# 7segment.net
KiCad netlist of a schematic drawn in EAGLE
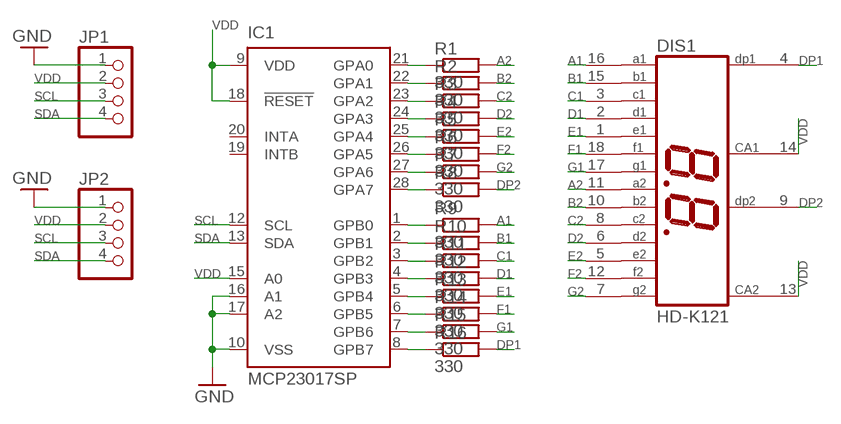
[diagram p0: schematic, sheet 1]

(export (version "E")
  (design (tool "Eeschema 10.0.6"))
  (components
    (comp (ref "DIS1")
      (value "HD-K121")
      (footprint "eagle-import:HDSP-R")
      (libsource (lib "eagle-import") (part "HD-K121"))
    )
    (comp (ref "IC1")
      (value "MCP23017SP")
      (footprint "eagle-import:DIL28-3")
      (fields (field (name "MF") "MICROCHIP") (field (name "MPN") "MCP23017-E/SP"))
      (libsource (lib "eagle-import") (part "MCP23017SP"))
    )
    (comp (ref "JP1")
      (value "PINHD-1X4")
      (footprint "eagle-import:1X04")
      (libsource (lib "eagle-import") (part "PINHD-1X4"))
    )
    (comp (ref "JP2")
      (value "PINHD-1X4")
      (footprint "eagle-import:1X04")
      (libsource (lib "eagle-import") (part "PINHD-1X4"))
    )
    (comp (ref "R1")
      (value "330")
      (footprint "eagle-import:0204V")
      (libsource (lib "eagle-import") (part "R-EU_0204/2V"))
    )
    (comp (ref "R2")
      (value "330")
      (footprint "eagle-import:0204V")
      (libsource (lib "eagle-import") (part "R-EU_0204/2V"))
    )
    (comp (ref "R3")
      (value "330")
      (footprint "eagle-import:0204V")
      (libsource (lib "eagle-import") (part "R-EU_0204/2V"))
    )
    (comp (ref "R4")
      (value "330")
      (footprint "eagle-import:0204V")
      (libsource (lib "eagle-import") (part "R-EU_0204/2V"))
    )
    (comp (ref "R5")
      (value "330")
      (footprint "eagle-import:0204V")
      (libsource (lib "eagle-import") (part "R-EU_0204/2V"))
    )
    (comp (ref "R6")
      (value "330")
      (footprint "eagle-import:0204V")
      (libsource (lib "eagle-import") (part "R-EU_0204/2V"))
    )
    (comp (ref "R7")
      (value "330")
      (footprint "eagle-import:0204V")
      (libsource (lib "eagle-import") (part "R-EU_0204/2V"))
    )
    (comp (ref "R8")
      (value "330")
      (footprint "eagle-import:0204V")
      (libsource (lib "eagle-import") (part "R-EU_0204/2V"))
    )
    (comp (ref "R9")
      (value "330")
      (footprint "eagle-import:0204V")
      (libsource (lib "eagle-import") (part "R-EU_0204/2V"))
    )
    (comp (ref "R10")
      (value "330")
      (footprint "eagle-import:0204V")
      (libsource (lib "eagle-import") (part "R-EU_0204/2V"))
    )
    (comp (ref "R11")
      (value "330")
      (footprint "eagle-import:0204V")
      (libsource (lib "eagle-import") (part "R-EU_0204/2V"))
    )
    (comp (ref "R12")
      (value "330")
      (footprint "eagle-import:0204V")
      (libsource (lib "eagle-import") (part "R-EU_0204/2V"))
    )
    (comp (ref "R13")
      (value "330")
      (footprint "eagle-import:0204V")
      (libsource (lib "eagle-import") (part "R-EU_0204/2V"))
    )
    (comp (ref "R14")
      (value "330")
      (footprint "eagle-import:0204V")
      (libsource (lib "eagle-import") (part "R-EU_0204/2V"))
    )
    (comp (ref "R15")
      (value "330")
      (footprint "eagle-import:0204V")
      (libsource (lib "eagle-import") (part "R-EU_0204/2V"))
    )
    (comp (ref "R16")
      (value "330")
      (footprint "eagle-import:0204V")
      (libsource (lib "eagle-import") (part "R-EU_0204/2V"))
    )
  )
  (nets
    (net (code "1") (name "/A1") (class "Default")
      (node (ref "DIS1") (pin "16") (pinfunction "A1_16") (pintype "passive"))
      (node (ref "R9") (pin "2") (pinfunction "2_2") (pintype "passive"))
    )
    (net (code "2") (name "/A2") (class "Default")
      (node (ref "DIS1") (pin "11") (pinfunction "A2_11") (pintype "passive"))
      (node (ref "R1") (pin "2") (pinfunction "2_2") (pintype "passive"))
    )
    (net (code "3") (name "/B1") (class "Default")
      (node (ref "DIS1") (pin "15") (pinfunction "B1_15") (pintype "passive"))
      (node (ref "R10") (pin "2") (pinfunction "2_2") (pintype "passive"))
    )
    (net (code "4") (name "/B2") (class "Default")
      (node (ref "DIS1") (pin "10") (pinfunction "B2_10") (pintype "passive"))
      (node (ref "R2") (pin "2") (pinfunction "2_2") (pintype "passive"))
    )
    (net (code "5") (name "/C1") (class "Default")
      (node (ref "DIS1") (pin "3") (pinfunction "C1_3") (pintype "passive"))
      (node (ref "R11") (pin "2") (pinfunction "2_2") (pintype "passive"))
    )
    (net (code "6") (name "/C2") (class "Default")
      (node (ref "DIS1") (pin "8") (pinfunction "C2_8") (pintype "passive"))
      (node (ref "R3") (pin "2") (pinfunction "2_2") (pintype "passive"))
    )
    (net (code "7") (name "/D1") (class "Default")
      (node (ref "DIS1") (pin "2") (pinfunction "D1_2") (pintype "passive"))
      (node (ref "R12") (pin "2") (pinfunction "2_2") (pintype "passive"))
    )
    (net (code "8") (name "/D2") (class "Default")
      (node (ref "DIS1") (pin "6") (pinfunction "D2_6") (pintype "passive"))
      (node (ref "R4") (pin "2") (pinfunction "2_2") (pintype "passive"))
    )
    (net (code "9") (name "/DP1") (class "Default")
      (node (ref "DIS1") (pin "4") (pinfunction "DP1_4") (pintype "passive"))
      (node (ref "R16") (pin "2") (pinfunction "2_2") (pintype "passive"))
    )
    (net (code "10") (name "/DP2") (class "Default")
      (node (ref "DIS1") (pin "9") (pinfunction "DP2_9") (pintype "passive"))
      (node (ref "R8") (pin "2") (pinfunction "2_2") (pintype "passive"))
    )
    (net (code "11") (name "/E1") (class "Default")
      (node (ref "DIS1") (pin "1") (pinfunction "E1_1") (pintype "passive"))
      (node (ref "R13") (pin "2") (pinfunction "2_2") (pintype "passive"))
    )
    (net (code "12") (name "/E2") (class "Default")
      (node (ref "DIS1") (pin "5") (pinfunction "E2_5") (pintype "passive"))
      (node (ref "R5") (pin "2") (pinfunction "2_2") (pintype "passive"))
    )
    (net (code "13") (name "/F1") (class "Default")
      (node (ref "DIS1") (pin "18") (pinfunction "F1_18") (pintype "passive"))
      (node (ref "R14") (pin "2") (pinfunction "2_2") (pintype "passive"))
    )
    (net (code "14") (name "/F2") (class "Default")
      (node (ref "DIS1") (pin "12") (pinfunction "F2_12") (pintype "passive"))
      (node (ref "R6") (pin "2") (pinfunction "2_2") (pintype "passive"))
    )
    (net (code "15") (name "/G1") (class "Default")
      (node (ref "DIS1") (pin "17") (pinfunction "G1_17") (pintype "passive"))
      (node (ref "R15") (pin "2") (pinfunction "2_2") (pintype "passive"))
    )
    (net (code "16") (name "/G2") (class "Default")
      (node (ref "DIS1") (pin "7") (pinfunction "G2_7") (pintype "passive"))
      (node (ref "R7") (pin "2") (pinfunction "2_2") (pintype "passive"))
    )
    (net (code "17") (name "/SCL") (class "Default")
      (node (ref "IC1") (pin "12") (pinfunction "SCL_12") (pintype "input"))
      (node (ref "JP1") (pin "3") (pinfunction "3_3") (pintype "passive"))
      (node (ref "JP2") (pin "3") (pinfunction "3_3") (pintype "passive"))
    )
    (net (code "18") (name "/SDA") (class "Default")
      (node (ref "IC1") (pin "13") (pinfunction "SDA_13") (pintype "bidirectional"))
      (node (ref "JP1") (pin "4") (pinfunction "4_4") (pintype "passive"))
      (node (ref "JP2") (pin "4") (pinfunction "4_4") (pintype "passive"))
    )
    (net (code "19") (name "/VDD") (class "Default")
      (node (ref "DIS1") (pin "13") (pinfunction "CA2_13") (pintype "passive"))
      (node (ref "DIS1") (pin "14") (pinfunction "CA1_14") (pintype "passive"))
      (node (ref "IC1") (pin "15") (pinfunction "A0_15") (pintype "input"))
      (node (ref "IC1") (pin "18") (pinfunction "~{RESET}_18") (pintype "input"))
      (node (ref "IC1") (pin "9") (pinfunction "VDD_9") (pintype "power_in"))
      (node (ref "JP1") (pin "2") (pinfunction "2_2") (pintype "passive"))
      (node (ref "JP2") (pin "2") (pinfunction "2_2") (pintype "passive"))
    )
    (net (code "20") (name "GND") (class "Default")
      (node (ref "IC1") (pin "10") (pinfunction "VSS_10") (pintype "power_in"))
      (node (ref "IC1") (pin "16") (pinfunction "A1_16") (pintype "input"))
      (node (ref "IC1") (pin "17") (pinfunction "A2_17") (pintype "input"))
      (node (ref "JP1") (pin "1") (pinfunction "1_1") (pintype "passive"))
      (node (ref "JP2") (pin "1") (pinfunction "1_1") (pintype "passive"))
    )
    (net (code "21") (name "Net-(IC1-GPA0)") (class "Default")
      (node (ref "IC1") (pin "21") (pinfunction "GPA0_21") (pintype "bidirectional"))
      (node (ref "R1") (pin "1") (pinfunction "1_1") (pintype "passive"))
    )
    (net (code "22") (name "Net-(IC1-GPA1)") (class "Default")
      (node (ref "IC1") (pin "22") (pinfunction "GPA1_22") (pintype "bidirectional"))
      (node (ref "R2") (pin "1") (pinfunction "1_1") (pintype "passive"))
    )
    (net (code "23") (name "Net-(IC1-GPA2)") (class "Default")
      (node (ref "IC1") (pin "23") (pinfunction "GPA2_23") (pintype "bidirectional"))
      (node (ref "R3") (pin "1") (pinfunction "1_1") (pintype "passive"))
    )
    (net (code "24") (name "Net-(IC1-GPA3)") (class "Default")
      (node (ref "IC1") (pin "24") (pinfunction "GPA3_24") (pintype "bidirectional"))
      (node (ref "R4") (pin "1") (pinfunction "1_1") (pintype "passive"))
    )
    (net (code "25") (name "Net-(IC1-GPA4)") (class "Default")
      (node (ref "IC1") (pin "25") (pinfunction "GPA4_25") (pintype "bidirectional"))
      (node (ref "R5") (pin "1") (pinfunction "1_1") (pintype "passive"))
    )
    (net (code "26") (name "Net-(IC1-GPA5)") (class "Default")
      (node (ref "IC1") (pin "26") (pinfunction "GPA5_26") (pintype "bidirectional"))
      (node (ref "R6") (pin "1") (pinfunction "1_1") (pintype "passive"))
    )
    (net (code "27") (name "Net-(IC1-GPA6)") (class "Default")
      (node (ref "IC1") (pin "27") (pinfunction "GPA6_27") (pintype "bidirectional"))
      (node (ref "R7") (pin "1") (pinfunction "1_1") (pintype "passive"))
    )
    (net (code "28") (name "Net-(IC1-GPA7)") (class "Default")
      (node (ref "IC1") (pin "28") (pinfunction "GPA7_28") (pintype "bidirectional"))
      (node (ref "R8") (pin "1") (pinfunction "1_1") (pintype "passive"))
    )
    (net (code "29") (name "Net-(IC1-GPB0)") (class "Default")
      (node (ref "IC1") (pin "1") (pinfunction "GPB0_1") (pintype "bidirectional"))
      (node (ref "R9") (pin "1") (pinfunction "1_1") (pintype "passive"))
    )
    (net (code "30") (name "Net-(IC1-GPB1)") (class "Default")
      (node (ref "IC1") (pin "2") (pinfunction "GPB1_2") (pintype "bidirectional"))
      (node (ref "R10") (pin "1") (pinfunction "1_1") (pintype "passive"))
    )
    (net (code "31") (name "Net-(IC1-GPB2)") (class "Default")
      (node (ref "IC1") (pin "3") (pinfunction "GPB2_3") (pintype "bidirectional"))
      (node (ref "R11") (pin "1") (pinfunction "1_1") (pintype "passive"))
    )
    (net (code "32") (name "Net-(IC1-GPB3)") (class "Default")
      (node (ref "IC1") (pin "4") (pinfunction "GPB3_4") (pintype "bidirectional"))
      (node (ref "R12") (pin "1") (pinfunction "1_1") (pintype "passive"))
    )
    (net (code "33") (name "Net-(IC1-GPB4)") (class "Default")
      (node (ref "IC1") (pin "5") (pinfunction "GPB4_5") (pintype "bidirectional"))
      (node (ref "R13") (pin "1") (pinfunction "1_1") (pintype "passive"))
    )
    (net (code "34") (name "Net-(IC1-GPB5)") (class "Default")
      (node (ref "IC1") (pin "6") (pinfunction "GPB5_6") (pintype "bidirectional"))
      (node (ref "R14") (pin "1") (pinfunction "1_1") (pintype "passive"))
    )
    (net (code "35") (name "Net-(IC1-GPB6)") (class "Default")
      (node (ref "IC1") (pin "7") (pinfunction "GPB6_7") (pintype "bidirectional"))
      (node (ref "R15") (pin "1") (pinfunction "1_1") (pintype "passive"))
    )
    (net (code "36") (name "Net-(IC1-GPB7)") (class "Default")
      (node (ref "IC1") (pin "8") (pinfunction "GPB7_8") (pintype "bidirectional"))
      (node (ref "R16") (pin "1") (pinfunction "1_1") (pintype "passive"))
    )
    (net (code "37") (name "unconnected-(IC1-INTA-Pad20)") (class "Default")
      (node (ref "IC1") (pin "20") (pinfunction "INTA_20") (pintype "output"))
    )
    (net (code "38") (name "unconnected-(IC1-INTB-Pad19)") (class "Default")
      (node (ref "IC1") (pin "19") (pinfunction "INTB_19") (pintype "output"))
    )
  )
)
